# RAM.net
KiCad netlist of a schematic drawn in Altium Designer
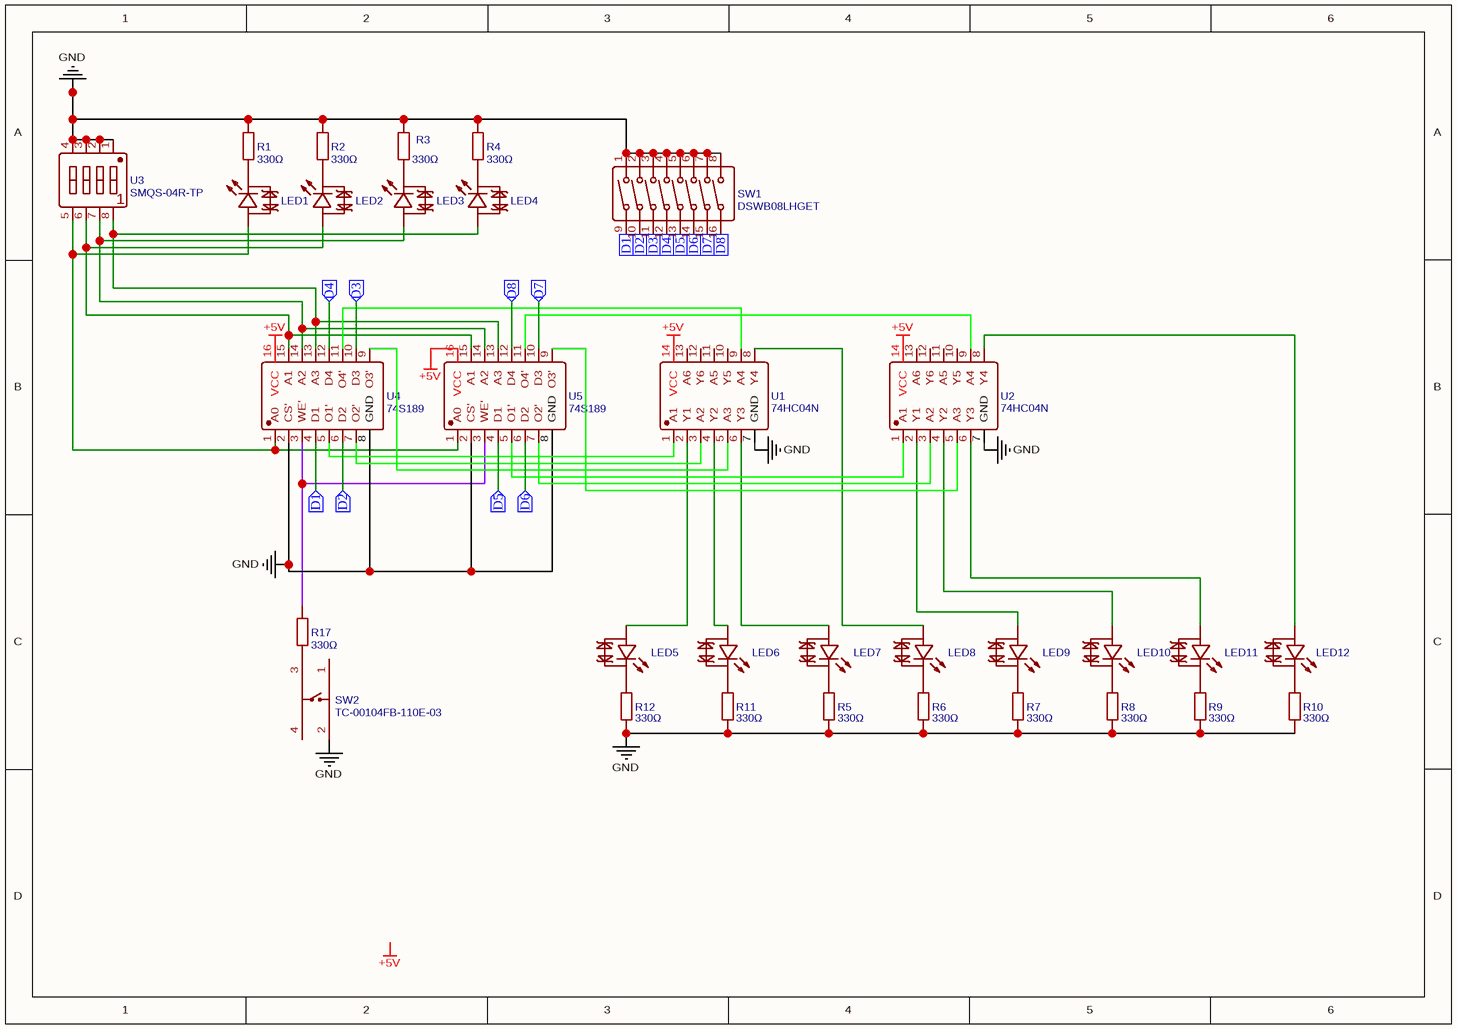
[diagram p0: RAM.schdoc]

(export (version "E")
  (design (tool "Eeschema 10.0.6"))
  (components
    (comp (ref "LED1")
      (value "204-15UTC/S400-X9-L")
      (fields (field (name "MANUFACTURER") "EVERLIGHT(亿光)") (field (name "CONTRIBUTOR") "LCSC"))
      (libsource (lib "altium-import") (part "root_1_204-15UTC/S400-X9-L_"))
    )
    (comp (ref "LED2")
      (value "204-15UTC/S400-X9-L")
      (fields (field (name "MANUFACTURER") "EVERLIGHT(亿光)") (field (name "CONTRIBUTOR") "LCSC"))
      (libsource (lib "altium-import") (part "root_1_204-15UTC/S400-X9-L_"))
    )
    (comp (ref "LED3")
      (value "204-15UTC/S400-X9-L")
      (fields (field (name "MANUFACTURER") "EVERLIGHT(亿光)") (field (name "CONTRIBUTOR") "LCSC"))
      (libsource (lib "altium-import") (part "root_1_204-15UTC/S400-X9-L_"))
    )
    (comp (ref "LED4")
      (value "204-15UTC/S400-X9-L")
      (fields (field (name "MANUFACTURER") "EVERLIGHT(亿光)") (field (name "CONTRIBUTOR") "LCSC"))
      (libsource (lib "altium-import") (part "root_1_204-15UTC/S400-X9-L_"))
    )
    (comp (ref "LED5")
      (value "204-15UTC/S400-X9-L")
      (fields (field (name "MANUFACTURER") "EVERLIGHT(亿光)") (field (name "CONTRIBUTOR") "LCSC"))
      (libsource (lib "altium-import") (part "root_3_204-15UTC/S400-X9-L_"))
    )
    (comp (ref "LED6")
      (value "204-15UTC/S400-X9-L")
      (fields (field (name "MANUFACTURER") "EVERLIGHT(亿光)") (field (name "CONTRIBUTOR") "LCSC"))
      (libsource (lib "altium-import") (part "root_3_204-15UTC/S400-X9-L_"))
    )
    (comp (ref "LED7")
      (value "204-15UTC/S400-X9-L")
      (fields (field (name "MANUFACTURER") "EVERLIGHT(亿光)") (field (name "CONTRIBUTOR") "LCSC"))
      (libsource (lib "altium-import") (part "root_3_204-15UTC/S400-X9-L_"))
    )
    (comp (ref "LED8")
      (value "204-15UTC/S400-X9-L")
      (fields (field (name "MANUFACTURER") "EVERLIGHT(亿光)") (field (name "CONTRIBUTOR") "LCSC"))
      (libsource (lib "altium-import") (part "root_3_204-15UTC/S400-X9-L_"))
    )
    (comp (ref "LED9")
      (value "204-15UTC/S400-X9-L")
      (fields (field (name "MANUFACTURER") "EVERLIGHT(亿光)") (field (name "CONTRIBUTOR") "LCSC"))
      (libsource (lib "altium-import") (part "root_3_204-15UTC/S400-X9-L_"))
    )
    (comp (ref "LED10")
      (value "204-15UTC/S400-X9-L")
      (fields (field (name "MANUFACTURER") "EVERLIGHT(亿光)") (field (name "CONTRIBUTOR") "LCSC"))
      (libsource (lib "altium-import") (part "root_3_204-15UTC/S400-X9-L_"))
    )
    (comp (ref "LED11")
      (value "204-15UTC/S400-X9-L")
      (fields (field (name "MANUFACTURER") "EVERLIGHT(亿光)") (field (name "CONTRIBUTOR") "LCSC"))
      (libsource (lib "altium-import") (part "root_3_204-15UTC/S400-X9-L_"))
    )
    (comp (ref "LED12")
      (value "204-15UTC/S400-X9-L")
      (fields (field (name "MANUFACTURER") "EVERLIGHT(亿光)") (field (name "CONTRIBUTOR") "LCSC"))
      (libsource (lib "altium-import") (part "root_3_204-15UTC/S400-X9-L_"))
    )
    (comp (ref "R1")
      (value "330Ω")
      (fields
        (field (name "MANUFACTURER") "CCO(千志电子)")
        (field (name "MANUFACTURER PART") "MF1/2W-0.1Ω±1% T")
        (field (name "CONTRIBUTOR") "LCSC")
      )
      (libsource (lib "altium-import") (part "root_1_330Ω_"))
    )
    (comp (ref "R2")
      (value "330Ω")
      (fields
        (field (name "MANUFACTURER") "CCO(千志电子)")
        (field (name "MANUFACTURER PART") "MF1/2W-0.1Ω±1% T")
        (field (name "CONTRIBUTOR") "LCSC")
      )
      (libsource (lib "altium-import") (part "root_1_330Ω_"))
    )
    (comp (ref "R3")
      (value "330Ω")
      (fields
        (field (name "MANUFACTURER") "CCO(千志电子)")
        (field (name "MANUFACTURER PART") "MF1/2W-0.1Ω±1% T")
        (field (name "CONTRIBUTOR") "LCSC")
      )
      (libsource (lib "altium-import") (part "root_1_330Ω_"))
    )
    (comp (ref "R4")
      (value "330Ω")
      (fields
        (field (name "MANUFACTURER") "CCO(千志电子)")
        (field (name "MANUFACTURER PART") "MF1/2W-0.1Ω±1% T")
        (field (name "CONTRIBUTOR") "LCSC")
      )
      (libsource (lib "altium-import") (part "root_1_330Ω_"))
    )
    (comp (ref "R5")
      (value "330Ω")
      (fields
        (field (name "MANUFACTURER") "CCO(千志电子)")
        (field (name "MANUFACTURER PART") "MF1/2W-0.1Ω±1% T")
        (field (name "CONTRIBUTOR") "LCSC")
      )
      (libsource (lib "altium-import") (part "root_3_330Ω_"))
    )
    (comp (ref "R6")
      (value "330Ω")
      (fields
        (field (name "MANUFACTURER") "CCO(千志电子)")
        (field (name "MANUFACTURER PART") "MF1/2W-0.1Ω±1% T")
        (field (name "CONTRIBUTOR") "LCSC")
      )
      (libsource (lib "altium-import") (part "root_3_330Ω_"))
    )
    (comp (ref "R7")
      (value "330Ω")
      (fields
        (field (name "MANUFACTURER") "CCO(千志电子)")
        (field (name "MANUFACTURER PART") "MF1/2W-0.1Ω±1% T")
        (field (name "CONTRIBUTOR") "LCSC")
      )
      (libsource (lib "altium-import") (part "root_3_330Ω_"))
    )
    (comp (ref "R8")
      (value "330Ω")
      (fields
        (field (name "MANUFACTURER") "CCO(千志电子)")
        (field (name "MANUFACTURER PART") "MF1/2W-0.1Ω±1% T")
        (field (name "CONTRIBUTOR") "LCSC")
      )
      (libsource (lib "altium-import") (part "root_3_330Ω_"))
    )
    (comp (ref "R9")
      (value "330Ω")
      (fields
        (field (name "MANUFACTURER") "CCO(千志电子)")
        (field (name "MANUFACTURER PART") "MF1/2W-0.1Ω±1% T")
        (field (name "CONTRIBUTOR") "LCSC")
      )
      (libsource (lib "altium-import") (part "root_3_330Ω_"))
    )
    (comp (ref "R10")
      (value "330Ω")
      (fields
        (field (name "MANUFACTURER") "CCO(千志电子)")
        (field (name "MANUFACTURER PART") "MF1/2W-0.1Ω±1% T")
        (field (name "CONTRIBUTOR") "LCSC")
      )
      (libsource (lib "altium-import") (part "root_3_330Ω_"))
    )
    (comp (ref "R11")
      (value "330Ω")
      (fields
        (field (name "MANUFACTURER") "CCO(千志电子)")
        (field (name "MANUFACTURER PART") "MF1/2W-0.1Ω±1% T")
        (field (name "CONTRIBUTOR") "LCSC")
      )
      (libsource (lib "altium-import") (part "root_3_330Ω_"))
    )
    (comp (ref "R12")
      (value "330Ω")
      (fields
        (field (name "MANUFACTURER") "CCO(千志电子)")
        (field (name "MANUFACTURER PART") "MF1/2W-0.1Ω±1% T")
        (field (name "CONTRIBUTOR") "LCSC")
      )
      (libsource (lib "altium-import") (part "root_3_330Ω_"))
    )
    (comp (ref "R17")
      (value "330Ω")
      (fields
        (field (name "MANUFACTURER") "CCO(千志电子)")
        (field (name "MANUFACTURER PART") "MF1/2W-0.1Ω±1% T")
        (field (name "CONTRIBUTOR") "LCSC")
      )
      (libsource (lib "altium-import") (part "root_3_330Ω_"))
    )
    (comp (ref "SW1")
      (value "DSWB08LHGET")
      (fields (field (name "MANUFACTURER") "YE") (field (name "CONTRIBUTOR") "LCSC"))
      (libsource (lib "altium-import") (part "root_0_DSWB08LHGET_"))
    )
    (comp (ref "SW2")
      (value "TC-00104FB-110E-03")
      (fields (field (name "MANUFACTURER") "HOOYA(皓宇电子)") (field (name "CONTRIBUTOR") "lcsc"))
      (libsource (lib "altium-import") (part "root_3_TC-00104FB-110E-03_"))
    )
    (comp (ref "U1")
      (value "74HC04N")
      (fields (field (name "MANUFACTURER") "HGSEMI(华冠)") (field (name "CONTRIBUTOR") "LCSC"))
      (libsource (lib "altium-import") (part "root_1_74HC04N_"))
    )
    (comp (ref "U2")
      (value "74HC04N")
      (fields (field (name "MANUFACTURER") "HGSEMI(华冠)") (field (name "CONTRIBUTOR") "LCSC"))
      (libsource (lib "altium-import") (part "root_1_74HC04N_"))
    )
    (comp (ref "U3")
      (value "SMQS-04R-TP")
      (fields (field (name "MANUFACTURER") "SM Switch") (field (name "CONTRIBUTOR") "lcsc"))
      (libsource (lib "altium-import") (part "root_3_SMQS-04R-TP_"))
    )
    (comp (ref "U4")
      (value "74S189")
      (fields (field (name "CONTRIBUTOR") "madhumathi.it22"))
      (libsource (lib "altium-import") (part "root_1_74S189_"))
    )
    (comp (ref "U5")
      (value "74S189")
      (fields (field (name "CONTRIBUTOR") "madhumathi.it22"))
      (libsource (lib "altium-import") (part "root_1_74S189_"))
    )
  )
  (nets
    (net (code "1") (name "+5V") (class "Default")
      (node (ref "U1") (pin "14") (pinfunction "VCC_14") (pintype "passive"))
      (node (ref "U2") (pin "14") (pinfunction "VCC_14") (pintype "passive"))
      (node (ref "U4") (pin "16") (pinfunction "VCC_16") (pintype "passive"))
      (node (ref "U5") (pin "16") (pinfunction "VCC_16") (pintype "passive"))
    )
    (net (code "2") (name "/D1") (class "Default")
      (node (ref "SW1") (pin "9") (pinfunction "9_9") (pintype "passive"))
      (node (ref "U4") (pin "4") (pinfunction "D1_4") (pintype "passive"))
    )
    (net (code "3") (name "/D2") (class "Default")
      (node (ref "SW1") (pin "10") (pinfunction "10_10") (pintype "passive"))
      (node (ref "U4") (pin "6") (pinfunction "D2_6") (pintype "passive"))
    )
    (net (code "4") (name "/D3") (class "Default")
      (node (ref "SW1") (pin "11") (pinfunction "11_11") (pintype "passive"))
      (node (ref "U4") (pin "10") (pinfunction "D3_10") (pintype "passive"))
    )
    (net (code "5") (name "/D4") (class "Default")
      (node (ref "SW1") (pin "12") (pinfunction "12_12") (pintype "passive"))
      (node (ref "U4") (pin "12") (pinfunction "D4_12") (pintype "passive"))
    )
    (net (code "6") (name "/D5") (class "Default")
      (node (ref "SW1") (pin "13") (pinfunction "13_13") (pintype "passive"))
      (node (ref "U5") (pin "4") (pinfunction "D1_4") (pintype "passive"))
    )
    (net (code "7") (name "/D6") (class "Default")
      (node (ref "SW1") (pin "14") (pinfunction "14_14") (pintype "passive"))
      (node (ref "U5") (pin "6") (pinfunction "D2_6") (pintype "passive"))
    )
    (net (code "8") (name "/D7") (class "Default")
      (node (ref "SW1") (pin "15") (pinfunction "15_15") (pintype "passive"))
      (node (ref "U5") (pin "10") (pinfunction "D3_10") (pintype "passive"))
    )
    (net (code "9") (name "/D8") (class "Default")
      (node (ref "SW1") (pin "16") (pinfunction "16_16") (pintype "passive"))
      (node (ref "U5") (pin "12") (pinfunction "D4_12") (pintype "passive"))
    )
    (net (code "10") (name "GND") (class "Default")
      (node (ref "R1") (pin "2") (pinfunction "2_2") (pintype "passive"))
      (node (ref "R10") (pin "2") (pinfunction "2_2") (pintype "passive"))
      (node (ref "R11") (pin "2") (pinfunction "2_2") (pintype "passive"))
      (node (ref "R12") (pin "2") (pinfunction "2_2") (pintype "passive"))
      (node (ref "R2") (pin "2") (pinfunction "2_2") (pintype "passive"))
      (node (ref "R3") (pin "2") (pinfunction "2_2") (pintype "passive"))
      (node (ref "R4") (pin "2") (pinfunction "2_2") (pintype "passive"))
      (node (ref "R5") (pin "2") (pinfunction "2_2") (pintype "passive"))
      (node (ref "R6") (pin "2") (pinfunction "2_2") (pintype "passive"))
      (node (ref "R7") (pin "2") (pinfunction "2_2") (pintype "passive"))
      (node (ref "R8") (pin "2") (pinfunction "2_2") (pintype "passive"))
      (node (ref "R9") (pin "2") (pinfunction "2_2") (pintype "passive"))
      (node (ref "SW1") (pin "1") (pinfunction "1_1") (pintype "passive"))
      (node (ref "SW1") (pin "2") (pinfunction "2_2") (pintype "passive"))
      (node (ref "SW1") (pin "3") (pinfunction "3_3") (pintype "passive"))
      (node (ref "SW1") (pin "4") (pinfunction "4_4") (pintype "passive"))
      (node (ref "SW1") (pin "5") (pinfunction "5_5") (pintype "passive"))
      (node (ref "SW1") (pin "6") (pinfunction "6_6") (pintype "passive"))
      (node (ref "SW1") (pin "7") (pinfunction "7_7") (pintype "passive"))
      (node (ref "SW1") (pin "8") (pinfunction "8_8") (pintype "passive"))
      (node (ref "SW2") (pin "2") (pinfunction "2_2") (pintype "passive"))
      (node (ref "U1") (pin "7") (pinfunction "GND_7") (pintype "passive"))
      (node (ref "U2") (pin "7") (pinfunction "GND_7") (pintype "passive"))
      (node (ref "U3") (pin "1") (pinfunction "PIN1_1") (pintype "passive"))
      (node (ref "U3") (pin "2") (pinfunction "PIN2_2") (pintype "passive"))
      (node (ref "U3") (pin "3") (pinfunction "PIN3_3") (pintype "passive"))
      (node (ref "U3") (pin "4") (pinfunction "PIN4_4") (pintype "passive"))
      (node (ref "U4") (pin "2") (pinfunction "CS'_2") (pintype "passive"))
      (node (ref "U4") (pin "8") (pinfunction "GND_8") (pintype "passive"))
      (node (ref "U5") (pin "2") (pinfunction "CS'_2") (pintype "passive"))
      (node (ref "U5") (pin "8") (pinfunction "GND_8") (pintype "passive"))
    )
    (net (code "11") (name "Net-(LED1-A)") (class "Default")
      (node (ref "LED1") (pin "1") (pinfunction "A_1") (pintype "passive"))
      (node (ref "U3") (pin "5") (pinfunction "PIN5_5") (pintype "passive"))
      (node (ref "U4") (pin "1") (pinfunction "A0_1") (pintype "passive"))
      (node (ref "U5") (pin "1") (pinfunction "A0_1") (pintype "passive"))
    )
    (net (code "12") (name "Net-(LED1-C)") (class "Default")
      (node (ref "LED1") (pin "2") (pinfunction "C_2") (pintype "passive"))
      (node (ref "R1") (pin "1") (pinfunction "1_1") (pintype "passive"))
    )
    (net (code "13") (name "Net-(LED2-A)") (class "Default")
      (node (ref "LED2") (pin "1") (pinfunction "A_1") (pintype "passive"))
      (node (ref "U3") (pin "6") (pinfunction "PIN6_6") (pintype "passive"))
      (node (ref "U4") (pin "15") (pinfunction "A1_15") (pintype "passive"))
      (node (ref "U5") (pin "15") (pinfunction "A1_15") (pintype "passive"))
    )
    (net (code "14") (name "Net-(LED2-C)") (class "Default")
      (node (ref "LED2") (pin "2") (pinfunction "C_2") (pintype "passive"))
      (node (ref "R2") (pin "1") (pinfunction "1_1") (pintype "passive"))
    )
    (net (code "15") (name "Net-(LED3-A)") (class "Default")
      (node (ref "LED3") (pin "1") (pinfunction "A_1") (pintype "passive"))
      (node (ref "U3") (pin "7") (pinfunction "PIN7_7") (pintype "passive"))
      (node (ref "U4") (pin "14") (pinfunction "A2_14") (pintype "passive"))
      (node (ref "U5") (pin "14") (pinfunction "A2_14") (pintype "passive"))
    )
    (net (code "16") (name "Net-(LED3-C)") (class "Default")
      (node (ref "LED3") (pin "2") (pinfunction "C_2") (pintype "passive"))
      (node (ref "R3") (pin "1") (pinfunction "1_1") (pintype "passive"))
    )
    (net (code "17") (name "Net-(LED4-A)") (class "Default")
      (node (ref "LED4") (pin "1") (pinfunction "A_1") (pintype "passive"))
      (node (ref "U3") (pin "8") (pinfunction "PIN8_8") (pintype "passive"))
      (node (ref "U4") (pin "13") (pinfunction "A3_13") (pintype "passive"))
      (node (ref "U5") (pin "13") (pinfunction "A3_13") (pintype "passive"))
    )
    (net (code "18") (name "Net-(LED4-C)") (class "Default")
      (node (ref "LED4") (pin "2") (pinfunction "C_2") (pintype "passive"))
      (node (ref "R4") (pin "1") (pinfunction "1_1") (pintype "passive"))
    )
    (net (code "19") (name "Net-(LED5-A)") (class "Default")
      (node (ref "LED5") (pin "1") (pinfunction "A_1") (pintype "passive"))
      (node (ref "U1") (pin "2") (pinfunction "Y1_2") (pintype "passive"))
    )
    (net (code "20") (name "Net-(LED5-C)") (class "Default")
      (node (ref "LED5") (pin "2") (pinfunction "C_2") (pintype "passive"))
      (node (ref "R12") (pin "1") (pinfunction "1_1") (pintype "passive"))
    )
    (net (code "21") (name "Net-(LED6-A)") (class "Default")
      (node (ref "LED6") (pin "1") (pinfunction "A_1") (pintype "passive"))
      (node (ref "U1") (pin "4") (pinfunction "Y2_4") (pintype "passive"))
    )
    (net (code "22") (name "Net-(LED6-C)") (class "Default")
      (node (ref "LED6") (pin "2") (pinfunction "C_2") (pintype "passive"))
      (node (ref "R11") (pin "1") (pinfunction "1_1") (pintype "passive"))
    )
    (net (code "23") (name "Net-(LED7-A)") (class "Default")
      (node (ref "LED7") (pin "1") (pinfunction "A_1") (pintype "passive"))
      (node (ref "U1") (pin "6") (pinfunction "Y3_6") (pintype "passive"))
    )
    (net (code "24") (name "Net-(LED7-C)") (class "Default")
      (node (ref "LED7") (pin "2") (pinfunction "C_2") (pintype "passive"))
      (node (ref "R5") (pin "1") (pinfunction "1_1") (pintype "passive"))
    )
    (net (code "25") (name "Net-(LED8-A)") (class "Default")
      (node (ref "LED8") (pin "1") (pinfunction "A_1") (pintype "passive"))
      (node (ref "U1") (pin "8") (pinfunction "Y4_8") (pintype "passive"))
    )
    (net (code "26") (name "Net-(LED8-C)") (class "Default")
      (node (ref "LED8") (pin "2") (pinfunction "C_2") (pintype "passive"))
      (node (ref "R6") (pin "1") (pinfunction "1_1") (pintype "passive"))
    )
    (net (code "27") (name "Net-(LED9-A)") (class "Default")
      (node (ref "LED9") (pin "1") (pinfunction "A_1") (pintype "passive"))
      (node (ref "U2") (pin "2") (pinfunction "Y1_2") (pintype "passive"))
    )
    (net (code "28") (name "Net-(LED9-C)") (class "Default")
      (node (ref "LED9") (pin "2") (pinfunction "C_2") (pintype "passive"))
      (node (ref "R7") (pin "1") (pinfunction "1_1") (pintype "passive"))
    )
    (net (code "29") (name "Net-(LED10-A)") (class "Default")
      (node (ref "LED10") (pin "1") (pinfunction "A_1") (pintype "passive"))
      (node (ref "U2") (pin "4") (pinfunction "Y2_4") (pintype "passive"))
    )
    (net (code "30") (name "Net-(LED10-C)") (class "Default")
      (node (ref "LED10") (pin "2") (pinfunction "C_2") (pintype "passive"))
      (node (ref "R8") (pin "1") (pinfunction "1_1") (pintype "passive"))
    )
    (net (code "31") (name "Net-(LED11-A)") (class "Default")
      (node (ref "LED11") (pin "1") (pinfunction "A_1") (pintype "passive"))
      (node (ref "U2") (pin "6") (pinfunction "Y3_6") (pintype "passive"))
    )
    (net (code "32") (name "Net-(LED11-C)") (class "Default")
      (node (ref "LED11") (pin "2") (pinfunction "C_2") (pintype "passive"))
      (node (ref "R9") (pin "1") (pinfunction "1_1") (pintype "passive"))
    )
    (net (code "33") (name "Net-(LED12-A)") (class "Default")
      (node (ref "LED12") (pin "1") (pinfunction "A_1") (pintype "passive"))
      (node (ref "U2") (pin "8") (pinfunction "Y4_8") (pintype "passive"))
    )
    (net (code "34") (name "Net-(LED12-C)") (class "Default")
      (node (ref "LED12") (pin "2") (pinfunction "C_2") (pintype "passive"))
      (node (ref "R10") (pin "1") (pinfunction "1_1") (pintype "passive"))
    )
    (net (code "35") (name "Net-(R17-Pad2)") (class "Default")
      (node (ref "R17") (pin "2") (pinfunction "2_2") (pintype "passive"))
      (node (ref "SW2") (pin "3") (pinfunction "3_3") (pintype "passive"))
    )
    (net (code "36") (name "Net-(U1-A1)") (class "Default")
      (node (ref "U1") (pin "1") (pinfunction "A1_1") (pintype "passive"))
      (node (ref "U4") (pin "5") (pinfunction "O1'_5") (pintype "passive"))
    )
    (net (code "37") (name "Net-(U1-A2)") (class "Default")
      (node (ref "U1") (pin "3") (pinfunction "A2_3") (pintype "passive"))
      (node (ref "U4") (pin "7") (pinfunction "O2'_7") (pintype "passive"))
    )
    (net (code "38") (name "Net-(U1-A3)") (class "Default")
      (node (ref "U1") (pin "5") (pinfunction "A3_5") (pintype "passive"))
      (node (ref "U4") (pin "9") (pinfunction "O3'_9") (pintype "passive"))
    )
    (net (code "39") (name "Net-(U1-A4)") (class "Default")
      (node (ref "U1") (pin "9") (pinfunction "A4_9") (pintype "passive"))
      (node (ref "U4") (pin "11") (pinfunction "O4'_11") (pintype "passive"))
    )
    (net (code "40") (name "Net-(U2-A1)") (class "Default")
      (node (ref "U2") (pin "1") (pinfunction "A1_1") (pintype "passive"))
      (node (ref "U5") (pin "5") (pinfunction "O1'_5") (pintype "passive"))
    )
    (net (code "41") (name "Net-(U2-A2)") (class "Default")
      (node (ref "U2") (pin "3") (pinfunction "A2_3") (pintype "passive"))
      (node (ref "U5") (pin "7") (pinfunction "O2'_7") (pintype "passive"))
    )
    (net (code "42") (name "Net-(U2-A3)") (class "Default")
      (node (ref "U2") (pin "5") (pinfunction "A3_5") (pintype "passive"))
      (node (ref "U5") (pin "9") (pinfunction "O3'_9") (pintype "passive"))
    )
    (net (code "43") (name "Net-(U2-A4)") (class "Default")
      (node (ref "U2") (pin "9") (pinfunction "A4_9") (pintype "passive"))
      (node (ref "U5") (pin "11") (pinfunction "O4'_11") (pintype "passive"))
    )
    (net (code "44") (name "Net-(U4-WE')") (class "Default")
      (node (ref "R17") (pin "1") (pinfunction "1_1") (pintype "passive"))
      (node (ref "U4") (pin "3") (pinfunction "WE'_3") (pintype "passive"))
      (node (ref "U5") (pin "3") (pinfunction "WE'_3") (pintype "passive"))
    )
    (net (code "45") (name "unconnected-(SW2-Pad1)") (class "Default")
      (node (ref "SW2") (pin "1") (pinfunction "1_1") (pintype "passive"))
    )
    (net (code "46") (name "unconnected-(SW2-Pad4)") (class "Default")
      (node (ref "SW2") (pin "4") (pinfunction "4_4") (pintype "passive"))
    )
    (net (code "47") (name "unconnected-(U1-A5-Pad11)") (class "Default")
      (node (ref "U1") (pin "11") (pinfunction "A5_11") (pintype "passive"))
    )
    (net (code "48") (name "unconnected-(U1-A6-Pad13)") (class "Default")
      (node (ref "U1") (pin "13") (pinfunction "A6_13") (pintype "passive"))
    )
    (net (code "49") (name "unconnected-(U1-Y5-Pad10)") (class "Default")
      (node (ref "U1") (pin "10") (pinfunction "Y5_10") (pintype "passive"))
    )
    (net (code "50") (name "unconnected-(U1-Y6-Pad12)") (class "Default")
      (node (ref "U1") (pin "12") (pinfunction "Y6_12") (pintype "passive"))
    )
    (net (code "51") (name "unconnected-(U2-A5-Pad11)") (class "Default")
      (node (ref "U2") (pin "11") (pinfunction "A5_11") (pintype "passive"))
    )
    (net (code "52") (name "unconnected-(U2-A6-Pad13)") (class "Default")
      (node (ref "U2") (pin "13") (pinfunction "A6_13") (pintype "passive"))
    )
    (net (code "53") (name "unconnected-(U2-Y5-Pad10)") (class "Default")
      (node (ref "U2") (pin "10") (pinfunction "Y5_10") (pintype "passive"))
    )
    (net (code "54") (name "unconnected-(U2-Y6-Pad12)") (class "Default")
      (node (ref "U2") (pin "12") (pinfunction "Y6_12") (pintype "passive"))
    )
  )
)
